# usb2jtag.net
KiCad netlist of a schematic drawn in Altium Designer
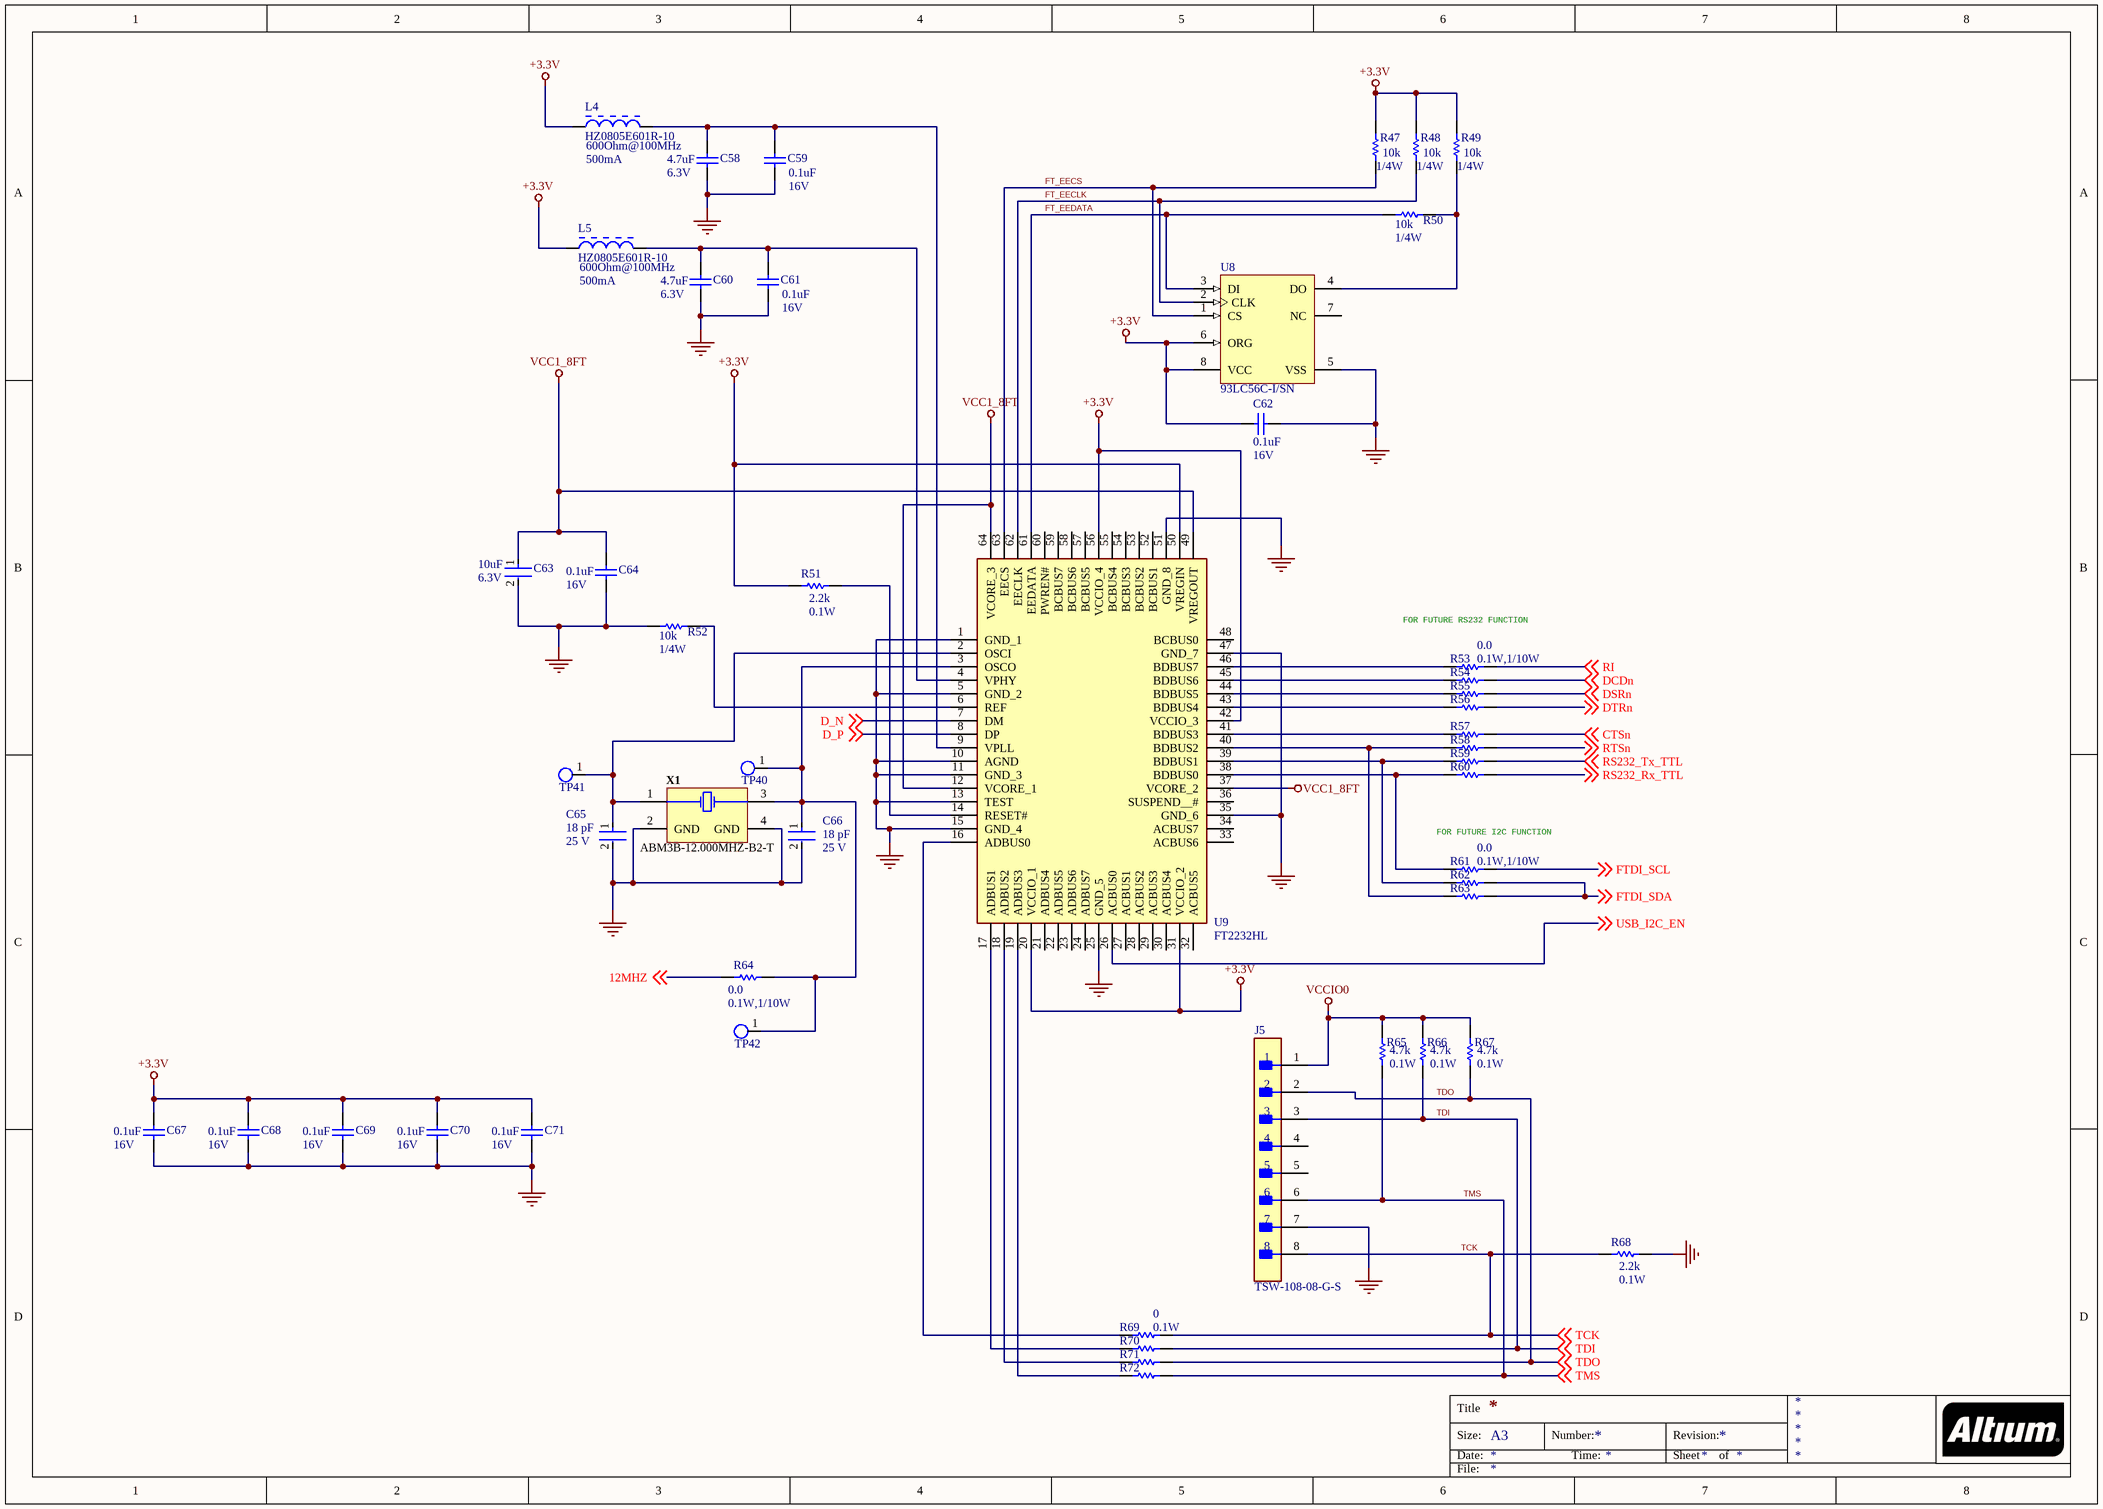
[diagram p0: usb2jtag.SchDoc]

(export (version "E")
  (design (tool "Eeschema 10.0.6"))
  (components
    (comp (ref "C58")
      (value "4.7uF")
      (footprint "CAPC2013X145X50NL20T25")
      (fields
        (field (name "PART NUMBER") "C0805C475K9PACTU")
        (field (name "MANUFACTURER") "Kemet")
        (field (name "VOLTAGE") "6.3V")
      )
      (libsource (lib "Altium Content Vault") (part "CAP"))
    )
    (comp (ref "C59")
      (value "0.1uF")
      (footprint "CAPC1608X87X35ML15T15")
      (description "Ceramic Capacitor 0.1uF 16V +-10% X7R0603")
      (fields
        (field (name "PART NUMBER") "C0603C104M4RACTU")
        (field (name "MANUFACTURER") "Kemet")
        (field (name "VOLTAGE") "16V")
      )
      (libsource (lib "Altium Content Vault") (part "CAP"))
    )
    (comp (ref "C60")
      (value "4.7uF")
      (footprint "CAPC2013X145X50NL20T25")
      (fields
        (field (name "PART NUMBER") "C0805C475K9PACTU")
        (field (name "MANUFACTURER") "Kemet")
        (field (name "VOLTAGE") "6.3V")
      )
      (libsource (lib "Altium Content Vault") (part "CAP"))
    )
    (comp (ref "C61")
      (value "0.1uF")
      (footprint "CAPC1608X87X35ML15T15")
      (description "Ceramic Capacitor 0.1uF 16V +-10% X7R0603")
      (fields
        (field (name "PART NUMBER") "C0603C104M4RACTU")
        (field (name "MANUFACTURER") "Kemet")
        (field (name "VOLTAGE") "16V")
      )
      (libsource (lib "Altium Content Vault") (part "CAP"))
    )
    (comp (ref "C62")
      (value "0.1uF")
      (footprint "CAPC1608X87X35ML15T15")
      (description "Ceramic Capacitor 0.1uF 16V +-10% X7R0603")
      (fields
        (field (name "PART NUMBER") "C0603C104M4RACTU")
        (field (name "MANUFACTURER") "Kemet")
        (field (name "VOLTAGE") "16V")
      )
      (libsource (lib "Altium Content Vault") (part "CAP"))
    )
    (comp (ref "C63")
      (value "10uF")
      (footprint "FP-CL10-IPC_C")
      (description "Cap Ceramic 10uF 6.3V X5R ±20% Pad SMD 0603 +85°C T/R")
      (fields
        (field (name "VOLTAGE") "6.3V")
        (field (name "TOLERANCE") "20%")
        (field (name "MANUFACTURER") "Samsung")
      )
      (libsource (lib "Altium Content Vault") (part "b4654b650e69147ec39a6b967a45e02"))
    )
    (comp (ref "C64")
      (value "0.1uF")
      (footprint "CAPC1608X87X35ML15T15")
      (description "Ceramic Capacitor 0.1uF 16V +-10% X7R0603")
      (fields
        (field (name "PART NUMBER") "C0603C104M4RACTU")
        (field (name "MANUFACTURER") "Kemet")
        (field (name "VOLTAGE") "16V")
      )
      (libsource (lib "Altium Content Vault") (part "CAP"))
    )
    (comp (ref "C65")
      (value "18 pF")
      (footprint "FP-C0603C-CF-MFG")
      (description "CAP CER 18PF 25V C0G/NP0 0603")
      (fields
        (field (name "TOLERANCE") "0.05")
        (field (name "MANUFACTURER") "KEMET")
        (field (name "VOLTAGE") "25 V")
      )
      (libsource (lib "Altium Content Vault") (part "b4654b650e69147ec39a6b967a45e02"))
    )
    (comp (ref "C66")
      (value "18 pF")
      (footprint "FP-C0603C-CF-MFG")
      (description "CAP CER 18PF 25V C0G/NP0 0603")
      (fields
        (field (name "TOLERANCE") "0.05")
        (field (name "MANUFACTURER") "KEMET")
        (field (name "VOLTAGE") "25 V")
      )
      (libsource (lib "Altium Content Vault") (part "b4654b650e69147ec39a6b967a45e02"))
    )
    (comp (ref "C67")
      (value "0.1uF")
      (footprint "CAPC1608X87X35ML15T15")
      (description "Ceramic Capacitor 0.1uF 16V +-10% X7R0603")
      (fields
        (field (name "PART NUMBER") "C0603C104M4RACTU")
        (field (name "MANUFACTURER") "Kemet")
        (field (name "VOLTAGE") "16V")
      )
      (libsource (lib "Altium Content Vault") (part "CAP"))
    )
    (comp (ref "C68")
      (value "0.1uF")
      (footprint "CAPC1608X87X35ML15T15")
      (description "Ceramic Capacitor 0.1uF 16V +-10% X7R0603")
      (fields
        (field (name "PART NUMBER") "C0603C104M4RACTU")
        (field (name "MANUFACTURER") "Kemet")
        (field (name "VOLTAGE") "16V")
      )
      (libsource (lib "Altium Content Vault") (part "CAP"))
    )
    (comp (ref "C69")
      (value "0.1uF")
      (footprint "CAPC1608X87X35ML15T15")
      (description "Ceramic Capacitor 0.1uF 16V +-10% X7R0603")
      (fields
        (field (name "PART NUMBER") "C0603C104M4RACTU")
        (field (name "MANUFACTURER") "Kemet")
        (field (name "VOLTAGE") "16V")
      )
      (libsource (lib "Altium Content Vault") (part "CAP"))
    )
    (comp (ref "C70")
      (value "0.1uF")
      (footprint "CAPC1608X87X35ML15T15")
      (description "Ceramic Capacitor 0.1uF 16V +-10% X7R0603")
      (fields
        (field (name "PART NUMBER") "C0603C104M4RACTU")
        (field (name "MANUFACTURER") "Kemet")
        (field (name "VOLTAGE") "16V")
      )
      (libsource (lib "Altium Content Vault") (part "CAP"))
    )
    (comp (ref "C71")
      (value "0.1uF")
      (footprint "CAPC1608X87X35ML15T15")
      (description "Ceramic Capacitor 0.1uF 16V +-10% X7R0603")
      (fields
        (field (name "PART NUMBER") "C0603C104M4RACTU")
        (field (name "MANUFACTURER") "Kemet")
        (field (name "VOLTAGE") "16V")
      )
      (libsource (lib "Altium Content Vault") (part "CAP"))
    )
    (comp (ref "J5")
      (value "TSW-108-08-G-S")
      (footprint "FP-TSW-108-08-G-S-MFG")
      (description "CONN HEADER VERT 8POS 2.54MM")
      (fields
        (field (name "MANUFACTURER") "Samtec")
        (field (name "OCTOPART") "https://octopart.com/tsw-108-08-g-s-samtec-272653")
      )
      (libsource (lib "Altium Content Vault") (part "99ec2b232beb5d2356d4d77f6a047f0"))
    )
    (comp (ref "L4")
      (value "HZ0805E601R-10")
      (footprint "LIRD-LI0805H151R-10-2_V")
      (fields
        (field (name "IMPEDANCE @ FREQUENCY") "600Ohm@100MHz")
        (field (name "MANUFACTURER") "Laird")
        (field (name "CURRENT RATING (MAX)") "500mA")
      )
      (libsource (lib "Altium Content Vault") (part "IND-FB-2"))
    )
    (comp (ref "L5")
      (value "HZ0805E601R-10")
      (footprint "LIRD-LI0805H151R-10-2_V")
      (fields
        (field (name "IMPEDANCE @ FREQUENCY") "600Ohm@100MHz")
        (field (name "MANUFACTURER") "Laird")
        (field (name "CURRENT RATING (MAX)") "500mA")
      )
      (libsource (lib "Altium Content Vault") (part "IND-FB-2"))
    )
    (comp (ref "R47")
      (value "10k")
      (footprint "RESC3216X70X50NL05T20")
      (description "Res Thick Film 1206 10k Ohms 5% 1/4W")
      (fields
        (field (name "PART NUMBER") "ERJ-8GEYJ103V")
        (field (name "MANUFACTURER") "Panasonic")
        (field (name "POWER") "1/4W")
      )
      (libsource (lib "Altium Content Vault") (part "RES"))
    )
    (comp (ref "R48")
      (value "10k")
      (footprint "RESC3216X70X50NL05T20")
      (description "Res Thick Film 1206 10k Ohms 5% 1/4W")
      (fields
        (field (name "PART NUMBER") "ERJ-8GEYJ103V")
        (field (name "MANUFACTURER") "Panasonic")
        (field (name "POWER") "1/4W")
      )
      (libsource (lib "Altium Content Vault") (part "RES"))
    )
    (comp (ref "R49")
      (value "10k")
      (footprint "RESC3216X70X50NL05T20")
      (description "Res Thick Film 1206 10k Ohms 5% 1/4W")
      (fields
        (field (name "PART NUMBER") "ERJ-8GEYJ103V")
        (field (name "MANUFACTURER") "Panasonic")
        (field (name "POWER") "1/4W")
      )
      (libsource (lib "Altium Content Vault") (part "RES"))
    )
    (comp (ref "R50")
      (value "10k")
      (footprint "RESC3216X70X50NL05T20")
      (description "Res Thick Film 1206 10k Ohms 5% 1/4W")
      (fields
        (field (name "PART NUMBER") "ERJ-8GEYJ103V")
        (field (name "MANUFACTURER") "Panasonic")
        (field (name "POWER") "1/4W")
      )
      (libsource (lib "Altium Content Vault") (part "RES"))
    )
    (comp (ref "R51")
      (value "2.2k")
      (footprint "RESC1608X55X25LL10T15")
      (fields
        (field (name "TOLERANCE") "1%")
        (field (name "VOLTAGE") "50V")
        (field (name "MANUFACTURER") "Yageo")
        (field (name "POWER") "0.1W")
      )
      (libsource (lib "Altium Content Vault") (part "RES-2"))
    )
    (comp (ref "R52")
      (value "10k")
      (footprint "RESC3216X70X50NL05T20")
      (description "Res Thick Film 1206 10k Ohms 5% 1/4W")
      (fields
        (field (name "PART NUMBER") "ERJ-8GEYJ103V")
        (field (name "MANUFACTURER") "Panasonic")
        (field (name "POWER") "1/4W")
      )
      (libsource (lib "Altium Content Vault") (part "RES"))
    )
    (comp (ref "R53")
      (value "0.0")
      (footprint "RESC1608X55X35LL10T10")
      (description "Chip Resistor, 0 Ohm, +/- 5%, 0.1 W, -55 to 155 degC, 0603 (1608 Metric), RoHS, Tape and Reel")
      (fields
        (field (name "POWER") "0.1W,1/10W")
        (field (name "MANUFACTURER") "Samsung-Electro-Mechanics-America,-Inc.")
        (field (name "TOLERANCE") "Jumper")
      )
      (libsource (lib "Altium Content Vault") (part "RES-2"))
    )
    (comp (ref "R54")
      (value "RC1608J000CS")
      (footprint "RESC1608X55X35LL10T10")
      (description "Chip Resistor, 0 Ohm, +/- 5%, 0.1 W, -55 to 155 degC, 0603 (1608 Metric), RoHS, Tape and Reel")
      (fields
        (field (name "POWER") "0.1W,1/10W")
        (field (name "MANUFACTURER") "Samsung-Electro-Mechanics-America,-Inc.")
      )
      (libsource (lib "Altium Content Vault") (part "RES-2"))
    )
    (comp (ref "R55")
      (value "RC1608J000CS")
      (footprint "RESC1608X55X35LL10T10")
      (description "Chip Resistor, 0 Ohm, +/- 5%, 0.1 W, -55 to 155 degC, 0603 (1608 Metric), RoHS, Tape and Reel")
      (fields
        (field (name "POWER") "0.1W,1/10W")
        (field (name "MANUFACTURER") "Samsung-Electro-Mechanics-America,-Inc.")
      )
      (libsource (lib "Altium Content Vault") (part "RES-2"))
    )
    (comp (ref "R56")
      (value "RC1608J000CS")
      (footprint "RESC1608X55X35LL10T10")
      (description "Chip Resistor, 0 Ohm, +/- 5%, 0.1 W, -55 to 155 degC, 0603 (1608 Metric), RoHS, Tape and Reel")
      (fields
        (field (name "POWER") "0.1W,1/10W")
        (field (name "MANUFACTURER") "Samsung-Electro-Mechanics-America,-Inc.")
      )
      (libsource (lib "Altium Content Vault") (part "RES-2"))
    )
    (comp (ref "R57")
      (value "RC1608J000CS")
      (footprint "RESC1608X55X35LL10T10")
      (description "Chip Resistor, 0 Ohm, +/- 5%, 0.1 W, -55 to 155 degC, 0603 (1608 Metric), RoHS, Tape and Reel")
      (fields
        (field (name "POWER") "0.1W,1/10W")
        (field (name "MANUFACTURER") "Samsung-Electro-Mechanics-America,-Inc.")
      )
      (libsource (lib "Altium Content Vault") (part "RES-2"))
    )
    (comp (ref "R58")
      (value "RC1608J000CS")
      (footprint "RESC1608X55X35LL10T10")
      (description "Chip Resistor, 0 Ohm, +/- 5%, 0.1 W, -55 to 155 degC, 0603 (1608 Metric), RoHS, Tape and Reel")
      (fields
        (field (name "POWER") "0.1W,1/10W")
        (field (name "MANUFACTURER") "Samsung-Electro-Mechanics-America,-Inc.")
      )
      (libsource (lib "Altium Content Vault") (part "RES-2"))
    )
    (comp (ref "R59")
      (value "RC1608J000CS")
      (footprint "RESC1608X55X35LL10T10")
      (description "Chip Resistor, 0 Ohm, +/- 5%, 0.1 W, -55 to 155 degC, 0603 (1608 Metric), RoHS, Tape and Reel")
      (fields
        (field (name "POWER") "0.1W,1/10W")
        (field (name "MANUFACTURER") "Samsung-Electro-Mechanics-America,-Inc.")
      )
      (libsource (lib "Altium Content Vault") (part "RES-2"))
    )
    (comp (ref "R60")
      (value "RC1608J000CS")
      (footprint "RESC1608X55X35LL10T10")
      (description "Chip Resistor, 0 Ohm, +/- 5%, 0.1 W, -55 to 155 degC, 0603 (1608 Metric), RoHS, Tape and Reel")
      (fields
        (field (name "POWER") "0.1W,1/10W")
        (field (name "MANUFACTURER") "Samsung-Electro-Mechanics-America,-Inc.")
      )
      (libsource (lib "Altium Content Vault") (part "RES-2"))
    )
    (comp (ref "R61")
      (value "0.0")
      (footprint "RESC1608X55X35LL10T10")
      (description "Chip Resistor, 0 Ohm, +/- 5%, 0.1 W, -55 to 155 degC, 0603 (1608 Metric), RoHS, Tape and Reel")
      (fields
        (field (name "POWER") "0.1W,1/10W")
        (field (name "MANUFACTURER") "Samsung-Electro-Mechanics-America,-Inc.")
        (field (name "TOLERANCE") "Jumper")
      )
      (libsource (lib "Altium Content Vault") (part "RES-2"))
    )
    (comp (ref "R62")
      (value "RC1608J000CS")
      (footprint "RESC1608X55X35LL10T10")
      (description "Chip Resistor, 0 Ohm, +/- 5%, 0.1 W, -55 to 155 degC, 0603 (1608 Metric), RoHS, Tape and Reel")
      (fields
        (field (name "POWER") "0.1W,1/10W")
        (field (name "MANUFACTURER") "Samsung-Electro-Mechanics-America,-Inc.")
      )
      (libsource (lib "Altium Content Vault") (part "RES-2"))
    )
    (comp (ref "R63")
      (value "RC1608J000CS")
      (footprint "RESC1608X55X35LL10T10")
      (description "Chip Resistor, 0 Ohm, +/- 5%, 0.1 W, -55 to 155 degC, 0603 (1608 Metric), RoHS, Tape and Reel")
      (fields
        (field (name "POWER") "0.1W,1/10W")
        (field (name "MANUFACTURER") "Samsung-Electro-Mechanics-America,-Inc.")
      )
      (libsource (lib "Altium Content Vault") (part "RES-2"))
    )
    (comp (ref "R64")
      (value "0.0")
      (footprint "RESC1608X55X35LL10T10")
      (description "Chip Resistor, 0 Ohm, +/- 5%, 0.1 W, -55 to 155 degC, 0603 (1608 Metric), RoHS, Tape and Reel")
      (fields
        (field (name "POWER") "0.1W,1/10W")
        (field (name "MANUFACTURER") "Samsung-Electro-Mechanics-America,-Inc.")
        (field (name "TOLERANCE") "Jumper")
      )
      (libsource (lib "Altium Content Vault") (part "RES-2"))
    )
    (comp (ref "R65")
      (value "4.7k")
      (footprint "RESC1608X55X25LL10T15")
      (description "Chip Resistor, 4.7 KOhm, +/- 1%, 0.1 W, -55 to 155 degC, 0603 (1608 Metric), RoHS, Tape and Reel")
      (fields
        (field (name "POWER") "0.1W")
        (field (name "MANUFACTURER") "Yageo")
        (field (name "TOLERANCE") "1%")
      )
      (libsource (lib "Altium Content Vault") (part "RES-2"))
    )
    (comp (ref "R66")
      (value "4.7k")
      (footprint "RESC1608X55X25LL10T15")
      (description "Chip Resistor, 4.7 KOhm, +/- 1%, 0.1 W, -55 to 155 degC, 0603 (1608 Metric), RoHS, Tape and Reel")
      (fields
        (field (name "POWER") "0.1W")
        (field (name "MANUFACTURER") "Yageo")
        (field (name "TOLERANCE") "1%")
      )
      (libsource (lib "Altium Content Vault") (part "RES-2"))
    )
    (comp (ref "R67")
      (value "4.7k")
      (footprint "RESC1608X55X25LL10T15")
      (description "Chip Resistor, 4.7 KOhm, +/- 1%, 0.1 W, -55 to 155 degC, 0603 (1608 Metric), RoHS, Tape and Reel")
      (fields
        (field (name "POWER") "0.1W")
        (field (name "MANUFACTURER") "Yageo")
        (field (name "TOLERANCE") "1%")
      )
      (libsource (lib "Altium Content Vault") (part "RES-2"))
    )
    (comp (ref "R68")
      (value "2.2k")
      (footprint "RESC1608X55X25LL10T15")
      (fields
        (field (name "TOLERANCE") "1%")
        (field (name "VOLTAGE") "50V")
        (field (name "MANUFACTURER") "Yageo")
        (field (name "POWER") "0.1W")
      )
      (libsource (lib "Altium Content Vault") (part "RES-2"))
    )
    (comp (ref "R69")
      (value "0")
      (footprint "RESC1609X50X30LL8T20")
      (description "Chip Resistor, 4.7 KOhm, +/- 1%, 100 mW, -55 to 155 degC, 0603 (1608 Metric), RoHS, Tape and Reel")
      (fields
        (field (name "MANUFACTURER") "Vishay")
        (field (name "PART NUMBER") "CRCW06034K70FKEA")
        (field (name "POWER") "0.1W")
      )
      (libsource (lib "Altium Content Vault") (part "RES-2"))
    )
    (comp (ref "R70")
      (value "CRCW06034K70FKEA")
      (footprint "RESC1609X50X30LL8T20")
      (description "Chip Resistor, 4.7 KOhm, +/- 1%, 100 mW, -55 to 155 degC, 0603 (1608 Metric), RoHS, Tape and Reel")
      (fields (field (name "MANUFACTURER") "Vishay") (field (name "POWER") "0.1W"))
      (libsource (lib "Altium Content Vault") (part "RES-2"))
    )
    (comp (ref "R71")
      (value "CRCW06034K70FKEA")
      (footprint "RESC1609X50X30LL8T20")
      (description "Chip Resistor, 4.7 KOhm, +/- 1%, 100 mW, -55 to 155 degC, 0603 (1608 Metric), RoHS, Tape and Reel")
      (fields (field (name "MANUFACTURER") "Vishay") (field (name "POWER") "0.1W"))
      (libsource (lib "Altium Content Vault") (part "RES-2"))
    )
    (comp (ref "R72")
      (value "CRCW06034K70FKEA")
      (footprint "RESC1609X50X30LL8T20")
      (description "Chip Resistor, 4.7 KOhm, +/- 1%, 100 mW, -55 to 155 degC, 0603 (1608 Metric), RoHS, Tape and Reel")
      (fields (field (name "MANUFACTURER") "Vishay") (field (name "POWER") "0.1W"))
      (libsource (lib "Altium Content Vault") (part "RES-2"))
    )
    (comp (ref "TP40")
      (value "Test_Point_SMD")
      (footprint "Test_Point_SMD")
      (libsource (lib "Edson") (part "Test_Point_SMD"))
    )
    (comp (ref "TP41")
      (value "Test_Point_SMD")
      (footprint "Test_Point_SMD")
      (libsource (lib "Edson") (part "Test_Point_SMD"))
    )
    (comp (ref "TP42")
      (value "Test_Point_SMD")
      (footprint "Test_Point_SMD")
      (libsource (lib "Edson") (part "Test_Point_SMD"))
    )
    (comp (ref "U8")
      (value "93LC56C-I/SN")
      (footprint "SOIC-SN8_L")
      (description "2K, 256x8 or 128x16-bit, 2.5V Microwire Serial EEPROM, 8-Pin SOIC 150mil, Industrial Temperature")
      (libsource (lib "Altium Content Vault") (part "MEM-SEEPROM-93AA46C-P-8"))
    )
    (comp (ref "U9")
      (value "FT2232HL")
      (footprint "SamacSys:QFP50P1200X1200X160-64N")
      (description "Integrated Circuit")
      (fields (field (name "MANUFACTURER") "FTDI Chip") (field (name "ARROW PART NUMBER") "FT2232HL-REEL"))
      (libsource (lib "*") (part "FT2232HL-REEL"))
    )
    (comp (ref "X1")
      (value "ABM3B-12.000MHZ-B2-T")
      (footprint "ABRA-ABM3B-4_V")
      (description "Ceramic SMD Crystal, 12 MHz, +/- 20 ppm, 70 Ohm, -20 to 70 degC, 4-Pin SMD, RoHS, Tape and Reel")
      (fields (field (name "MANUFACTURER") "Abracon"))
      (libsource (lib "Altium Content Vault") (part "XTAL-1-3-4"))
    )
  )
  (nets
    (net (code "1") (name "+3.3V") (class "Default")
      (node (ref "C62") (pin "2") (pinfunction "2_2") (pintype "passive"))
      (node (ref "C67") (pin "2") (pinfunction "2_2") (pintype "passive"))
      (node (ref "C68") (pin "2") (pinfunction "2_2") (pintype "passive"))
      (node (ref "C69") (pin "2") (pinfunction "2_2") (pintype "passive"))
      (node (ref "C70") (pin "2") (pinfunction "2_2") (pintype "passive"))
      (node (ref "C71") (pin "2") (pinfunction "2_2") (pintype "passive"))
      (node (ref "L4") (pin "1") (pinfunction "1_1") (pintype "passive"))
      (node (ref "L5") (pin "1") (pinfunction "1_1") (pintype "passive"))
      (node (ref "R47") (pin "2") (pinfunction "2_2") (pintype "passive"))
      (node (ref "R48") (pin "2") (pinfunction "2_2") (pintype "passive"))
      (node (ref "R49") (pin "2") (pinfunction "2_2") (pintype "passive"))
      (node (ref "R51") (pin "1") (pinfunction "1_1") (pintype "passive"))
      (node (ref "U8") (pin "6") (pinfunction "ORG_6") (pintype "input"))
      (node (ref "U8") (pin "8") (pinfunction "VCC_8") (pintype "power_in"))
      (node (ref "U9") (pin "20") (pinfunction "VCCIO_1_20") (pintype "passive"))
      (node (ref "U9") (pin "31") (pinfunction "VCCIO_2_31") (pintype "passive"))
      (node (ref "U9") (pin "42") (pinfunction "VCCIO_3_42") (pintype "passive"))
      (node (ref "U9") (pin "50") (pinfunction "VREGIN_50") (pintype "passive"))
      (node (ref "U9") (pin "56") (pinfunction "VCCIO_4_56") (pintype "passive"))
    )
    (net (code "2") (name "/FT_EECLK") (class "Default")
      (node (ref "R48") (pin "1") (pinfunction "1_1") (pintype "passive"))
      (node (ref "U8") (pin "2") (pinfunction "CLK_2") (pintype "input"))
      (node (ref "U9") (pin "62") (pinfunction "EECLK_62") (pintype "passive"))
    )
    (net (code "3") (name "/FT_EECS") (class "Default")
      (node (ref "R47") (pin "1") (pinfunction "1_1") (pintype "passive"))
      (node (ref "U8") (pin "1") (pinfunction "CS_1") (pintype "input"))
      (node (ref "U9") (pin "63") (pinfunction "EECS_63") (pintype "passive"))
    )
    (net (code "4") (name "/FT_EEDATA") (class "Default")
      (node (ref "R50") (pin "2") (pinfunction "2_2") (pintype "passive"))
      (node (ref "U8") (pin "3") (pinfunction "DI_3") (pintype "input"))
      (node (ref "U9") (pin "61") (pinfunction "EEDATA_61") (pintype "passive"))
    )
    (net (code "5") (name "12MHZ") (class "Default")
      (node (ref "R64") (pin "1") (pinfunction "1_1") (pintype "passive"))
    )
    (net (code "6") (name "CTSn") (class "Default")
      (node (ref "R57") (pin "2") (pinfunction "2_2") (pintype "passive"))
    )
    (net (code "7") (name "DCDn") (class "Default")
      (node (ref "R54") (pin "2") (pinfunction "2_2") (pintype "passive"))
    )
    (net (code "8") (name "DSRn") (class "Default")
      (node (ref "R55") (pin "2") (pinfunction "2_2") (pintype "passive"))
    )
    (net (code "9") (name "DTRn") (class "Default")
      (node (ref "R56") (pin "2") (pinfunction "2_2") (pintype "passive"))
    )
    (net (code "10") (name "D_N") (class "Default")
      (node (ref "U9") (pin "7") (pinfunction "DM_7") (pintype "passive"))
    )
    (net (code "11") (name "D_P") (class "Default")
      (node (ref "U9") (pin "8") (pinfunction "DP_8") (pintype "passive"))
    )
    (net (code "12") (name "FTDI_SCL") (class "Default")
      (node (ref "R61") (pin "2") (pinfunction "2_2") (pintype "passive"))
    )
    (net (code "13") (name "FTDI_SDA") (class "Default")
      (node (ref "R62") (pin "2") (pinfunction "2_2") (pintype "passive"))
      (node (ref "R63") (pin "2") (pinfunction "2_2") (pintype "passive"))
    )
    (net (code "14") (name "GND") (class "Default")
      (node (ref "C58") (pin "1") (pinfunction "1_1") (pintype "passive"))
      (node (ref "C59") (pin "1") (pinfunction "1_1") (pintype "passive"))
      (node (ref "C60") (pin "1") (pinfunction "1_1") (pintype "passive"))
      (node (ref "C61") (pin "1") (pinfunction "1_1") (pintype "passive"))
      (node (ref "C62") (pin "1") (pinfunction "1_1") (pintype "passive"))
      (node (ref "C63") (pin "2") (pinfunction "2_2") (pintype "passive"))
      (node (ref "C64") (pin "1") (pinfunction "1_1") (pintype "passive"))
      (node (ref "C65") (pin "2") (pinfunction "2_2") (pintype "passive"))
      (node (ref "C66") (pin "2") (pinfunction "2_2") (pintype "passive"))
      (node (ref "C67") (pin "1") (pinfunction "1_1") (pintype "passive"))
      (node (ref "C68") (pin "1") (pinfunction "1_1") (pintype "passive"))
      (node (ref "C69") (pin "1") (pinfunction "1_1") (pintype "passive"))
      (node (ref "C70") (pin "1") (pinfunction "1_1") (pintype "passive"))
      (node (ref "C71") (pin "1") (pinfunction "1_1") (pintype "passive"))
      (node (ref "J5") (pin "7") (pinfunction "7_7") (pintype "passive"))
      (node (ref "R52") (pin "2") (pinfunction "2_2") (pintype "passive"))
      (node (ref "R68") (pin "2") (pinfunction "2_2") (pintype "passive"))
      (node (ref "U8") (pin "5") (pinfunction "VSS_5") (pintype "power_in"))
      (node (ref "U9") (pin "1") (pinfunction "GND_1_1") (pintype "passive"))
      (node (ref "U9") (pin "10") (pinfunction "AGND_10") (pintype "passive"))
      (node (ref "U9") (pin "11") (pinfunction "GND_3_11") (pintype "passive"))
      (node (ref "U9") (pin "13") (pinfunction "TEST_13") (pintype "passive"))
      (node (ref "U9") (pin "15") (pinfunction "GND_4_15") (pintype "passive"))
      (node (ref "U9") (pin "25") (pinfunction "GND_5_25") (pintype "passive"))
      (node (ref "U9") (pin "35") (pinfunction "GND_6_35") (pintype "passive"))
      (node (ref "U9") (pin "47") (pinfunction "GND_7_47") (pintype "passive"))
      (node (ref "U9") (pin "5") (pinfunction "GND_2_5") (pintype "passive"))
      (node (ref "U9") (pin "51") (pinfunction "GND_8_51") (pintype "passive"))
      (node (ref "X1") (pin "2") (pinfunction "GND_2") (pintype "power_in"))
      (node (ref "X1") (pin "4") (pinfunction "GND_4") (pintype "power_in"))
    )
    (net (code "15") (name "Net-(TP40-TP)") (class "Default")
      (node (ref "C66") (pin "1") (pinfunction "1_1") (pintype "passive"))
      (node (ref "R64") (pin "2") (pinfunction "2_2") (pintype "passive"))
      (node (ref "TP40") (pin "1") (pinfunction "TP_1") (pintype "passive"))
      (node (ref "TP42") (pin "1") (pinfunction "TP_1") (pintype "passive"))
      (node (ref "U9") (pin "3") (pinfunction "OSCO_3") (pintype "passive"))
      (node (ref "X1") (pin "3") (pinfunction "X2_3") (pintype "passive"))
    )
    (net (code "16") (name "Net-(TP41-TP)") (class "Default")
      (node (ref "C65") (pin "1") (pinfunction "1_1") (pintype "passive"))
      (node (ref "TP41") (pin "1") (pinfunction "TP_1") (pintype "passive"))
      (node (ref "U9") (pin "2") (pinfunction "OSCI_2") (pintype "passive"))
      (node (ref "X1") (pin "1") (pinfunction "X1_1") (pintype "passive"))
    )
    (net (code "17") (name "Net-(U8-DO)") (class "Default")
      (node (ref "R49") (pin "1") (pinfunction "1_1") (pintype "passive"))
      (node (ref "R50") (pin "1") (pinfunction "1_1") (pintype "passive"))
      (node (ref "U8") (pin "4") (pinfunction "DO_4") (pintype "tri_state"))
    )
    (net (code "18") (name "Net-(U9-ADBUS0)") (class "Default")
      (node (ref "R69") (pin "2") (pinfunction "2_2") (pintype "passive"))
      (node (ref "U9") (pin "16") (pinfunction "ADBUS0_16") (pintype "passive"))
    )
    (net (code "19") (name "Net-(U9-ADBUS1)") (class "Default")
      (node (ref "R70") (pin "2") (pinfunction "2_2") (pintype "passive"))
      (node (ref "U9") (pin "17") (pinfunction "ADBUS1_17") (pintype "passive"))
    )
    (net (code "20") (name "Net-(U9-ADBUS2)") (class "Default")
      (node (ref "R71") (pin "2") (pinfunction "2_2") (pintype "passive"))
      (node (ref "U9") (pin "18") (pinfunction "ADBUS2_18") (pintype "passive"))
    )
    (net (code "21") (name "Net-(U9-ADBUS3)") (class "Default")
      (node (ref "R72") (pin "2") (pinfunction "2_2") (pintype "passive"))
      (node (ref "U9") (pin "19") (pinfunction "ADBUS3_19") (pintype "passive"))
    )
    (net (code "22") (name "Net-(U9-BDBUS0)") (class "Default")
      (node (ref "R60") (pin "1") (pinfunction "1_1") (pintype "passive"))
      (node (ref "R61") (pin "1") (pinfunction "1_1") (pintype "passive"))
      (node (ref "U9") (pin "38") (pinfunction "BDBUS0_38") (pintype "passive"))
    )
    (net (code "23") (name "Net-(U9-BDBUS1)") (class "Default")
      (node (ref "R59") (pin "1") (pinfunction "1_1") (pintype "passive"))
      (node (ref "R62") (pin "1") (pinfunction "1_1") (pintype "passive"))
      (node (ref "U9") (pin "39") (pinfunction "BDBUS1_39") (pintype "passive"))
    )
    (net (code "24") (name "Net-(U9-BDBUS2)") (class "Default")
      (node (ref "R58") (pin "1") (pinfunction "1_1") (pintype "passive"))
      (node (ref "R63") (pin "1") (pinfunction "1_1") (pintype "passive"))
      (node (ref "U9") (pin "40") (pinfunction "BDBUS2_40") (pintype "passive"))
    )
    (net (code "25") (name "Net-(U9-BDBUS3)") (class "Default")
      (node (ref "R57") (pin "1") (pinfunction "1_1") (pintype "passive"))
      (node (ref "U9") (pin "41") (pinfunction "BDBUS3_41") (pintype "passive"))
    )
    (net (code "26") (name "Net-(U9-BDBUS4)") (class "Default")
      (node (ref "R56") (pin "1") (pinfunction "1_1") (pintype "passive"))
      (node (ref "U9") (pin "43") (pinfunction "BDBUS4_43") (pintype "passive"))
    )
    (net (code "27") (name "Net-(U9-BDBUS5)") (class "Default")
      (node (ref "R55") (pin "1") (pinfunction "1_1") (pintype "passive"))
      (node (ref "U9") (pin "44") (pinfunction "BDBUS5_44") (pintype "passive"))
    )
    (net (code "28") (name "Net-(U9-BDBUS6)") (class "Default")
      (node (ref "R54") (pin "1") (pinfunction "1_1") (pintype "passive"))
      (node (ref "U9") (pin "45") (pinfunction "BDBUS6_45") (pintype "passive"))
    )
    (net (code "29") (name "Net-(U9-BDBUS7)") (class "Default")
      (node (ref "R53") (pin "1") (pinfunction "1_1") (pintype "passive"))
      (node (ref "U9") (pin "46") (pinfunction "BDBUS7_46") (pintype "passive"))
    )
    (net (code "30") (name "Net-(U9-REF)") (class "Default")
      (node (ref "R52") (pin "1") (pinfunction "1_1") (pintype "passive"))
      (node (ref "U9") (pin "6") (pinfunction "REF_6") (pintype "passive"))
    )
    (net (code "31") (name "Net-(U9-RESET#)") (class "Default")
      (node (ref "R51") (pin "2") (pinfunction "2_2") (pintype "passive"))
      (node (ref "U9") (pin "14") (pinfunction "RESET#_14") (pintype "passive"))
    )
    (net (code "32") (name "Net-(U9-VPHY)") (class "Default")
      (node (ref "C60") (pin "2") (pinfunction "2_2") (pintype "passive"))
      (node (ref "C61") (pin "2") (pinfunction "2_2") (pintype "passive"))
      (node (ref "L5") (pin "2") (pinfunction "2_2") (pintype "passive"))
      (node (ref "U9") (pin "4") (pinfunction "VPHY_4") (pintype "passive"))
    )
    (net (code "33") (name "Net-(U9-VPLL)") (class "Default")
      (node (ref "C58") (pin "2") (pinfunction "2_2") (pintype "passive"))
      (node (ref "C59") (pin "2") (pinfunction "2_2") (pintype "passive"))
      (node (ref "L4") (pin "2") (pinfunction "2_2") (pintype "passive"))
      (node (ref "U9") (pin "9") (pinfunction "VPLL_9") (pintype "passive"))
    )
    (net (code "34") (name "RI") (class "Default")
      (node (ref "R53") (pin "2") (pinfunction "2_2") (pintype "passive"))
    )
    (net (code "35") (name "RS232_Rx_TTL") (class "Default")
      (node (ref "R60") (pin "2") (pinfunction "2_2") (pintype "passive"))
    )
    (net (code "36") (name "RS232_Tx_TTL") (class "Default")
      (node (ref "R59") (pin "2") (pinfunction "2_2") (pintype "passive"))
    )
    (net (code "37") (name "RTSn") (class "Default")
      (node (ref "R58") (pin "2") (pinfunction "2_2") (pintype "passive"))
    )
    (net (code "38") (name "TCK") (class "Default")
      (node (ref "J5") (pin "8") (pinfunction "8_8") (pintype "passive"))
      (node (ref "R68") (pin "1") (pinfunction "1_1") (pintype "passive"))
      (node (ref "R69") (pin "1") (pinfunction "1_1") (pintype "passive"))
    )
    (net (code "39") (name "TDI") (class "Default")
      (node (ref "J5") (pin "3") (pinfunction "3_3") (pintype "passive"))
      (node (ref "R66") (pin "1") (pinfunction "1_1") (pintype "passive"))
      (node (ref "R70") (pin "1") (pinfunction "1_1") (pintype "passive"))
    )
    (net (code "40") (name "TDO") (class "Default")
      (node (ref "J5") (pin "2") (pinfunction "2_2") (pintype "passive"))
      (node (ref "R67") (pin "1") (pinfunction "1_1") (pintype "passive"))
      (node (ref "R71") (pin "1") (pinfunction "1_1") (pintype "passive"))
    )
    (net (code "41") (name "TMS") (class "Default")
      (node (ref "J5") (pin "6") (pinfunction "6_6") (pintype "passive"))
      (node (ref "R65") (pin "1") (pinfunction "1_1") (pintype "passive"))
      (node (ref "R72") (pin "1") (pinfunction "1_1") (pintype "passive"))
    )
    (net (code "42") (name "USB_I2C_EN") (class "Default")
      (node (ref "U9") (pin "26") (pinfunction "ACBUS0_26") (pintype "passive"))
    )
    (net (code "43") (name "VCC1_8FT") (class "Default")
      (node (ref "C63") (pin "1") (pinfunction "1_1") (pintype "passive"))
      (node (ref "C64") (pin "2") (pinfunction "2_2") (pintype "passive"))
      (node (ref "U9") (pin "12") (pinfunction "VCORE_1_12") (pintype "passive"))
      (node (ref "U9") (pin "37") (pinfunction "VCORE_2_37") (pintype "passive"))
      (node (ref "U9") (pin "49") (pinfunction "VREGOUT_49") (pintype "passive"))
      (node (ref "U9") (pin "64") (pinfunction "VCORE_3_64") (pintype "passive"))
    )
    (net (code "44") (name "VCCIO0") (class "Default")
      (node (ref "J5") (pin "1") (pinfunction "1_1") (pintype "passive"))
      (node (ref "R65") (pin "2") (pinfunction "2_2") (pintype "passive"))
      (node (ref "R66") (pin "2") (pinfunction "2_2") (pintype "passive"))
      (node (ref "R67") (pin "2") (pinfunction "2_2") (pintype "passive"))
    )
    (net (code "45") (name "unconnected-(J5-Pad4)") (class "Default")
      (node (ref "J5") (pin "4") (pinfunction "4_4") (pintype "passive"))
    )
    (net (code "46") (name "unconnected-(J5-Pad5)") (class "Default")
      (node (ref "J5") (pin "5") (pinfunction "5_5") (pintype "passive"))
    )
    (net (code "47") (name "unconnected-(U8-NC-Pad7)") (class "Default")
      (node (ref "U8") (pin "7") (pinfunction "NC_7") (pintype "passive"))
    )
    (net (code "48") (name "unconnected-(U9-ACBUS1-Pad27)") (class "Default")
      (node (ref "U9") (pin "27") (pinfunction "ACBUS1_27") (pintype "passive"))
    )
    (net (code "49") (name "unconnected-(U9-ACBUS2-Pad28)") (class "Default")
      (node (ref "U9") (pin "28") (pinfunction "ACBUS2_28") (pintype "passive"))
    )
    (net (code "50") (name "unconnected-(U9-ACBUS3-Pad29)") (class "Default")
      (node (ref "U9") (pin "29") (pinfunction "ACBUS3_29") (pintype "passive"))
    )
    (net (code "51") (name "unconnected-(U9-ACBUS4-Pad30)") (class "Default")
      (node (ref "U9") (pin "30") (pinfunction "ACBUS4_30") (pintype "passive"))
    )
    (net (code "52") (name "unconnected-(U9-ACBUS5-Pad32)") (class "Default")
      (node (ref "U9") (pin "32") (pinfunction "ACBUS5_32") (pintype "passive"))
    )
    (net (code "53") (name "unconnected-(U9-ACBUS6-Pad33)") (class "Default")
      (node (ref "U9") (pin "33") (pinfunction "ACBUS6_33") (pintype "passive"))
    )
    (net (code "54") (name "unconnected-(U9-ACBUS7-Pad34)") (class "Default")
      (node (ref "U9") (pin "34") (pinfunction "ACBUS7_34") (pintype "passive"))
    )
    (net (code "55") (name "unconnected-(U9-ADBUS4-Pad21)") (class "Default")
      (node (ref "U9") (pin "21") (pinfunction "ADBUS4_21") (pintype "passive"))
    )
    (net (code "56") (name "unconnected-(U9-ADBUS5-Pad22)") (class "Default")
      (node (ref "U9") (pin "22") (pinfunction "ADBUS5_22") (pintype "passive"))
    )
    (net (code "57") (name "unconnected-(U9-ADBUS6-Pad23)") (class "Default")
      (node (ref "U9") (pin "23") (pinfunction "ADBUS6_23") (pintype "passive"))
    )
    (net (code "58") (name "unconnected-(U9-ADBUS7-Pad24)") (class "Default")
      (node (ref "U9") (pin "24") (pinfunction "ADBUS7_24") (pintype "passive"))
    )
    (net (code "59") (name "unconnected-(U9-BCBUS0-Pad48)") (class "Default")
      (node (ref "U9") (pin "48") (pinfunction "BCBUS0_48") (pintype "passive"))
    )
    (net (code "60") (name "unconnected-(U9-BCBUS1-Pad52)") (class "Default")
      (node (ref "U9") (pin "52") (pinfunction "BCBUS1_52") (pintype "passive"))
    )
    (net (code "61") (name "unconnected-(U9-BCBUS2-Pad53)") (class "Default")
      (node (ref "U9") (pin "53") (pinfunction "BCBUS2_53") (pintype "passive"))
    )
    (net (code "62") (name "unconnected-(U9-BCBUS3-Pad54)") (class "Default")
      (node (ref "U9") (pin "54") (pinfunction "BCBUS3_54") (pintype "passive"))
    )
    (net (code "63") (name "unconnected-(U9-BCBUS4-Pad55)") (class "Default")
      (node (ref "U9") (pin "55") (pinfunction "BCBUS4_55") (pintype "passive"))
    )
    (net (code "64") (name "unconnected-(U9-BCBUS5-Pad57)") (class "Default")
      (node (ref "U9") (pin "57") (pinfunction "BCBUS5_57") (pintype "passive"))
    )
    (net (code "65") (name "unconnected-(U9-BCBUS6-Pad58)") (class "Default")
      (node (ref "U9") (pin "58") (pinfunction "BCBUS6_58") (pintype "passive"))
    )
    (net (code "66") (name "unconnected-(U9-BCBUS7-Pad59)") (class "Default")
      (node (ref "U9") (pin "59") (pinfunction "BCBUS7_59") (pintype "passive"))
    )
    (net (code "67") (name "unconnected-(U9-PWREN#-Pad60)") (class "Default")
      (node (ref "U9") (pin "60") (pinfunction "PWREN#_60") (pintype "passive"))
    )
    (net (code "68") (name "unconnected-(U9-SUSPEND__#-Pad36)") (class "Default")
      (node (ref "U9") (pin "36") (pinfunction "SUSPEND__#_36") (pintype "passive"))
    )
  )
)
